# LoRa_Sensor_RevB.net
KiCad netlist of a schematic drawn in EAGLE
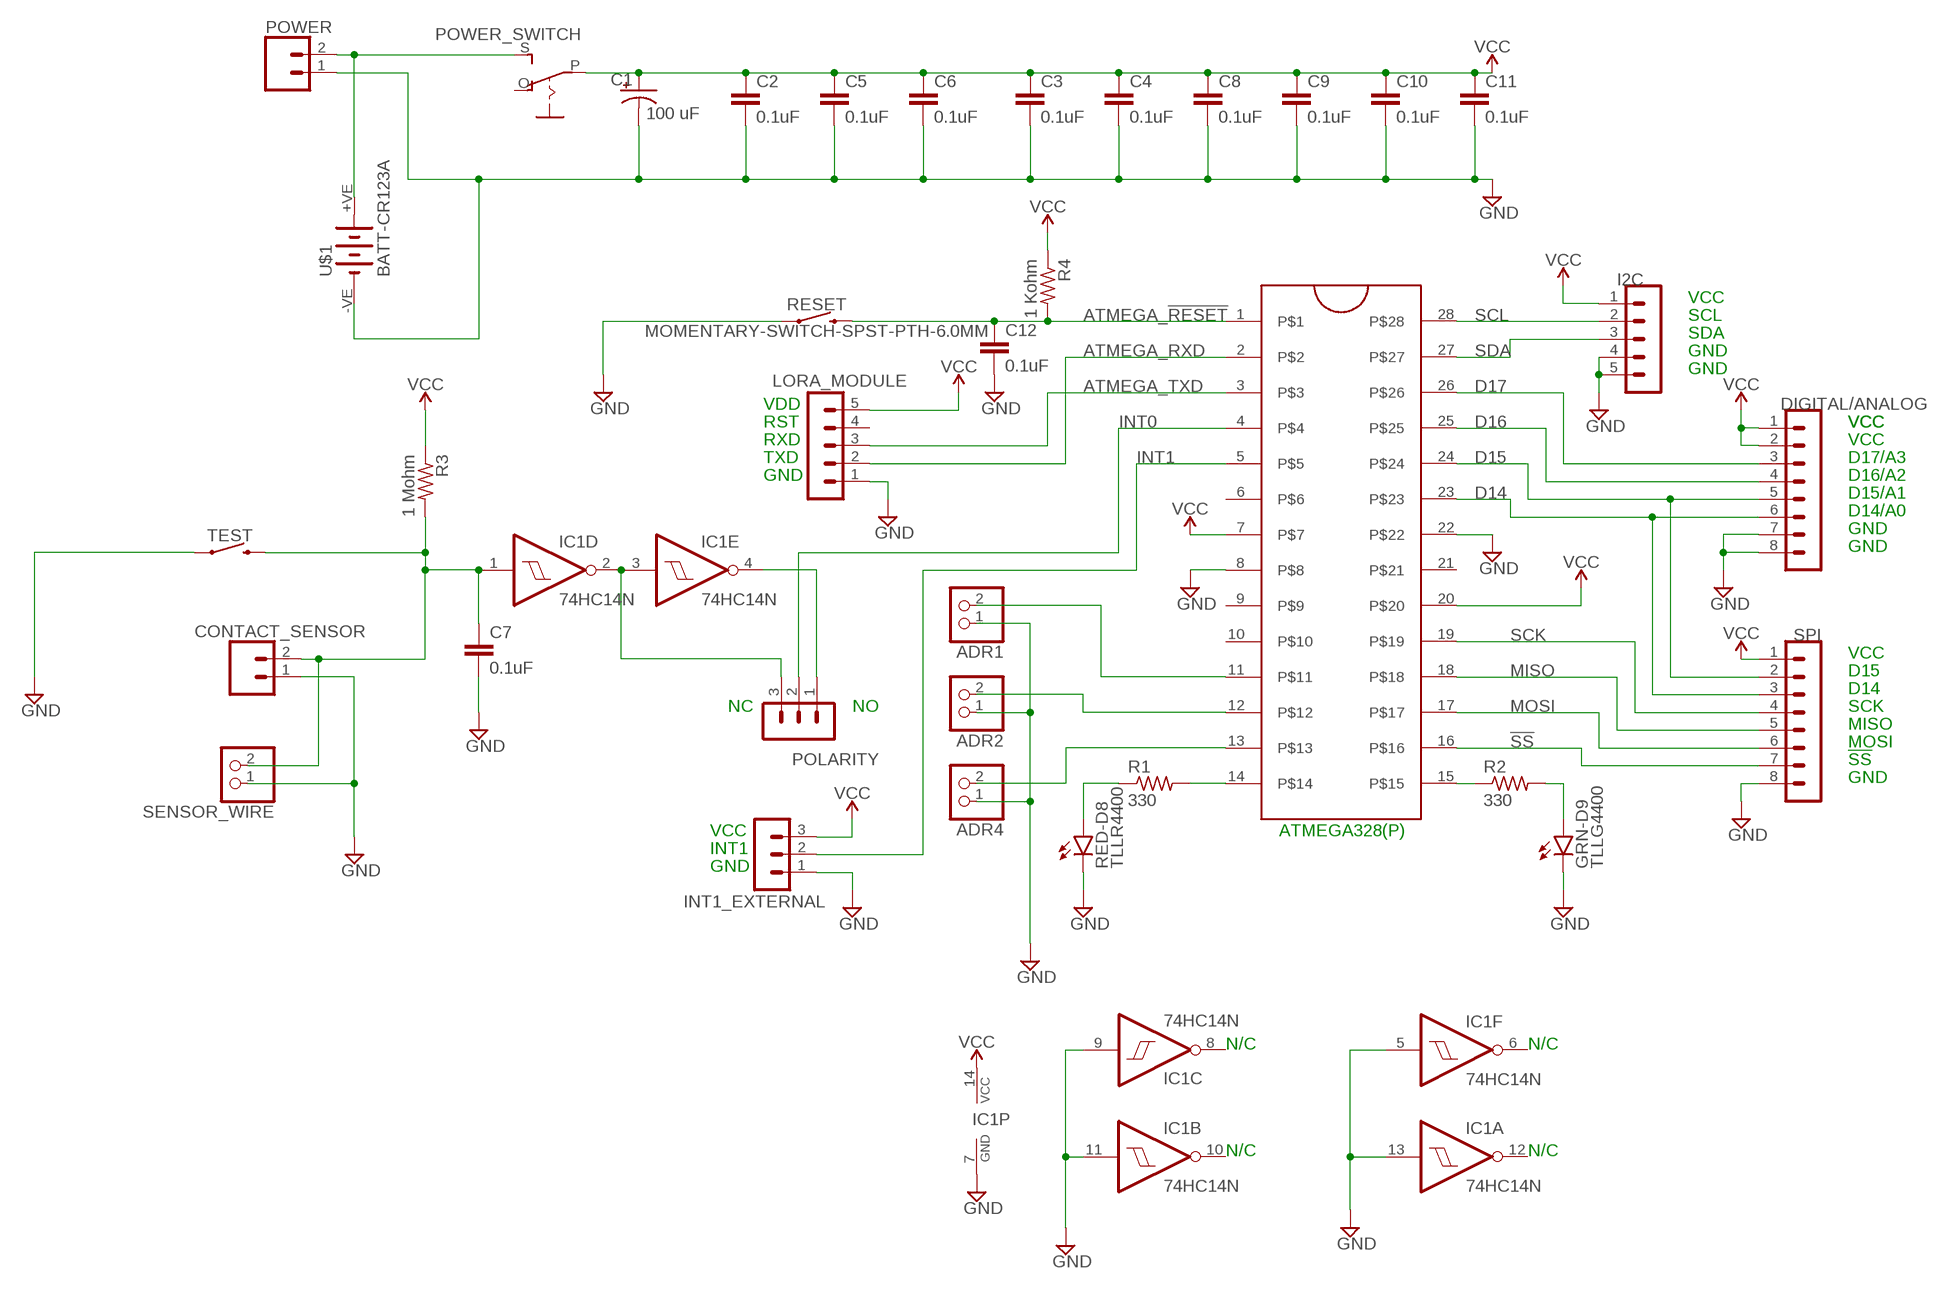
[diagram p0: schematic, sheet 2]

(export (version "E")
  (design (tool "Eeschema 10.0.6"))
  (components
    (comp (ref "ADR1")
      (value "PINHD-1X2")
      (footprint "eagle-import:1X02")
      (libsource (lib "eagle-import") (part "PINHD-1X2"))
    )
    (comp (ref "ADR2")
      (value "PINHD-1X2")
      (footprint "eagle-import:1X02")
      (libsource (lib "eagle-import") (part "PINHD-1X2"))
    )
    (comp (ref "ADR4")
      (value "PINHD-1X2")
      (footprint "eagle-import:1X02")
      (libsource (lib "eagle-import") (part "PINHD-1X2"))
    )
    (comp (ref "C1")
      (value "100 uF")
      (footprint "eagle-import:E2,5-6")
      (libsource (lib "eagle-import") (part "CPOL-USE2.5-6"))
    )
    (comp (ref "C2")
      (value "0.1uF")
      (footprint "eagle-import:CAP-PTH-SMALL-KIT")
      (libsource (lib "eagle-import") (part "0.1UF-KIT-EZ-50V-20%"))
    )
    (comp (ref "C3")
      (value "0.1uF")
      (footprint "eagle-import:CAP-PTH-SMALL-KIT")
      (libsource (lib "eagle-import") (part "0.1UF-KIT-EZ-50V-20%"))
    )
    (comp (ref "C4")
      (value "0.1uF")
      (footprint "eagle-import:CAP-PTH-SMALL-KIT")
      (libsource (lib "eagle-import") (part "0.1UF-KIT-EZ-50V-20%"))
    )
    (comp (ref "C5")
      (value "0.1uF")
      (footprint "eagle-import:CAP-PTH-SMALL-KIT")
      (libsource (lib "eagle-import") (part "0.1UF-KIT-EZ-50V-20%"))
    )
    (comp (ref "C6")
      (value "0.1uF")
      (footprint "eagle-import:CAP-PTH-SMALL-KIT")
      (libsource (lib "eagle-import") (part "0.1UF-KIT-EZ-50V-20%"))
    )
    (comp (ref "C7")
      (value "0.1uF")
      (footprint "eagle-import:CAP-PTH-SMALL-KIT")
      (libsource (lib "eagle-import") (part "0.1UF-KIT-EZ-50V-20%"))
    )
    (comp (ref "C8")
      (value "0.1uF")
      (footprint "eagle-import:CAP-PTH-SMALL-KIT")
      (libsource (lib "eagle-import") (part "0.1UF-KIT-EZ-50V-20%"))
    )
    (comp (ref "C9")
      (value "0.1uF")
      (footprint "eagle-import:CAP-PTH-SMALL-KIT")
      (libsource (lib "eagle-import") (part "0.1UF-KIT-EZ-50V-20%"))
    )
    (comp (ref "C10")
      (value "0.1uF")
      (footprint "eagle-import:CAP-PTH-SMALL-KIT")
      (libsource (lib "eagle-import") (part "0.1UF-KIT-EZ-50V-20%"))
    )
    (comp (ref "C11")
      (value "0.1uF")
      (footprint "eagle-import:CAP-PTH-SMALL-KIT")
      (libsource (lib "eagle-import") (part "0.1UF-KIT-EZ-50V-20%"))
    )
    (comp (ref "C12")
      (value "0.1uF")
      (footprint "eagle-import:CAP-PTH-SMALL-KIT")
      (libsource (lib "eagle-import") (part "0.1UF-KIT-EZ-50V-20%"))
    )
    (comp (ref "CONTACT_SENSOR")
      (value "CONN_023.5MM")
      (footprint "eagle-import:SCREWTERMINAL-3.5MM-2")
      (libsource (lib "eagle-import") (part "CONN_023.5MM"))
    )
    (comp (ref "DIGITAL/ANALOG")
      (value "MA08-1")
      (footprint "eagle-import:MA08-1")
      (libsource (lib "eagle-import") (part "MA08-1"))
    )
    (comp (ref "GRN-D9")
      (value "TLLG4400")
      (footprint "eagle-import:LED3MM")
      (fields (field (name "MF") "VISHAY SEMICONDUCTOR"))
      (libsource (lib "eagle-import") (part "TLLG4400"))
    )
    (comp (ref "I2C")
      (value "MA05-1")
      (footprint "eagle-import:MA05-1")
      (libsource (lib "eagle-import") (part "MA05-1"))
    )
    (comp (ref "IC1")
      (value "74HC14N")
      (footprint "eagle-import:DIL14")
      (libsource (lib "eagle-import") (part "7414NHC"))
    )
    (comp (ref "INT1_EXTERNAL")
      (value "MA03-1")
      (footprint "eagle-import:MA03-1")
      (libsource (lib "eagle-import") (part "MA03-1"))
    )
    (comp (ref "J1")
      (value "ZIFSOCKET-28-3\"")
      (footprint "eagle-import:DIL28-3-ZIF_SOCKET")
      (libsource (lib "eagle-import") (part "ZIFSOCKET-28-3{dblquote}"))
    )
    (comp (ref "LORA_MODULE")
      (value "MA05-1")
      (footprint "eagle-import:MA05-1")
      (libsource (lib "eagle-import") (part "MA05-1"))
    )
    (comp (ref "POLARITY")
      (value "MA03-1")
      (footprint "eagle-import:MA03-1")
      (libsource (lib "eagle-import") (part "MA03-1"))
    )
    (comp (ref "POWER")
      (value "CONN_023.5MM")
      (footprint "eagle-import:SCREWTERMINAL-3.5MM-2")
      (libsource (lib "eagle-import") (part "CONN_023.5MM"))
    )
    (comp (ref "POWER_SWITCH")
      (value "EG1218S")
      (footprint "eagle-import:EG1218")
      (libsource (lib "eagle-import") (part "EG1218S"))
    )
    (comp (ref "R1")
      (value "330")
      (footprint "eagle-import:0309_12")
      (libsource (lib "eagle-import") (part "R-US_0309/12"))
    )
    (comp (ref "R2")
      (value "330")
      (footprint "eagle-import:0309_12")
      (libsource (lib "eagle-import") (part "R-US_0309/12"))
    )
    (comp (ref "R3")
      (value "1 Mohm")
      (footprint "eagle-import:0309_12")
      (libsource (lib "eagle-import") (part "R-US_0309/12"))
    )
    (comp (ref "R4")
      (value "1 Kohm")
      (footprint "eagle-import:0309_12")
      (libsource (lib "eagle-import") (part "R-US_0309/12"))
    )
    (comp (ref "RED-D8")
      (value "TLLR4400")
      (footprint "eagle-import:LED3MM")
      (fields (field (name "MF") "VISHAY SEMICONDUCTOR"))
      (libsource (lib "eagle-import") (part "TLLR4400"))
    )
    (comp (ref "RESET")
      (value "MOMENTARY-SWITCH-SPST-PTH-6.0MM")
      (footprint "eagle-import:TACTILE_SWITCH_PTH_6.0MM")
      (libsource (lib "eagle-import") (part "MOMENTARY-SWITCH-SPST-PTH-6.0MM"))
    )
    (comp (ref "SENSOR_WIRE")
      (value "PINHD-1X2")
      (footprint "eagle-import:1X02")
      (libsource (lib "eagle-import") (part "PINHD-1X2"))
    )
    (comp (ref "SPI")
      (value "MA08-1")
      (footprint "eagle-import:MA08-1")
      (libsource (lib "eagle-import") (part "MA08-1"))
    )
    (comp (ref "TEST")
      (value "MOMENTARY-SWITCH-SPST-PTH-6.0MM")
      (footprint "eagle-import:TACTILE_SWITCH_PTH_6.0MM")
      (libsource (lib "eagle-import") (part "MOMENTARY-SWITCH-SPST-PTH-6.0MM"))
    )
    (comp (ref "U$1")
      (value "BATT-CR123A")
      (footprint "eagle-import:KEYSTONE-2_3A")
      (libsource (lib "eagle-import") (part "BATT-CR123A"))
    )
  )
  (nets
    (net (code "1") (name "ATMEGA_RXD") (class "Default")
      (node (ref "J1") (pin "2") (pinfunction "P$2_2") (pintype "bidirectional"))
      (node (ref "LORA_MODULE") (pin "2") (pinfunction "2_2") (pintype "passive"))
    )
    (net (code "2") (name "ATMEGA_TXD") (class "Default")
      (node (ref "J1") (pin "3") (pinfunction "P$3_3") (pintype "bidirectional"))
      (node (ref "LORA_MODULE") (pin "3") (pinfunction "3_3") (pintype "passive"))
    )
    (net (code "3") (name "ATMEGA_~{RESET}") (class "Default")
      (node (ref "C12") (pin "1") (pinfunction "1_1") (pintype "passive"))
      (node (ref "J1") (pin "1") (pinfunction "P$1_1") (pintype "bidirectional"))
      (node (ref "R4") (pin "2") (pinfunction "2_2") (pintype "passive"))
      (node (ref "RESET") (pin "3") (pinfunction "2_3") (pintype "passive"))
    )
    (net (code "4") (name "D14") (class "Default")
      (node (ref "DIGITAL/ANALOG") (pin "6") (pinfunction "6_6") (pintype "passive"))
      (node (ref "J1") (pin "23") (pinfunction "P$23_23") (pintype "bidirectional"))
      (node (ref "SPI") (pin "3") (pinfunction "3_3") (pintype "passive"))
    )
    (net (code "5") (name "D15") (class "Default")
      (node (ref "DIGITAL/ANALOG") (pin "5") (pinfunction "5_5") (pintype "passive"))
      (node (ref "J1") (pin "24") (pinfunction "P$24_24") (pintype "bidirectional"))
      (node (ref "SPI") (pin "2") (pinfunction "2_2") (pintype "passive"))
    )
    (net (code "6") (name "D16") (class "Default")
      (node (ref "DIGITAL/ANALOG") (pin "4") (pinfunction "4_4") (pintype "passive"))
      (node (ref "J1") (pin "25") (pinfunction "P$25_25") (pintype "bidirectional"))
    )
    (net (code "7") (name "D17") (class "Default")
      (node (ref "DIGITAL/ANALOG") (pin "3") (pinfunction "3_3") (pintype "passive"))
      (node (ref "J1") (pin "26") (pinfunction "P$26_26") (pintype "bidirectional"))
    )
    (net (code "8") (name "GND") (class "Default")
      (node (ref "ADR1") (pin "1") (pinfunction "1_1") (pintype "passive"))
      (node (ref "ADR2") (pin "1") (pinfunction "1_1") (pintype "passive"))
      (node (ref "ADR4") (pin "1") (pinfunction "1_1") (pintype "passive"))
      (node (ref "C1") (pin "-") (pinfunction "-_-") (pintype "passive"))
      (node (ref "C10") (pin "2") (pinfunction "2_2") (pintype "passive"))
      (node (ref "C11") (pin "2") (pinfunction "2_2") (pintype "passive"))
      (node (ref "C12") (pin "2") (pinfunction "2_2") (pintype "passive"))
      (node (ref "C2") (pin "2") (pinfunction "2_2") (pintype "passive"))
      (node (ref "C3") (pin "2") (pinfunction "2_2") (pintype "passive"))
      (node (ref "C4") (pin "2") (pinfunction "2_2") (pintype "passive"))
      (node (ref "C5") (pin "2") (pinfunction "2_2") (pintype "passive"))
      (node (ref "C6") (pin "2") (pinfunction "2_2") (pintype "passive"))
      (node (ref "C7") (pin "2") (pinfunction "2_2") (pintype "passive"))
      (node (ref "C8") (pin "2") (pinfunction "2_2") (pintype "passive"))
      (node (ref "C9") (pin "2") (pinfunction "2_2") (pintype "passive"))
      (node (ref "CONTACT_SENSOR") (pin "1") (pinfunction "1_1") (pintype "passive"))
      (node (ref "DIGITAL/ANALOG") (pin "7") (pinfunction "7_7") (pintype "passive"))
      (node (ref "DIGITAL/ANALOG") (pin "8") (pinfunction "8_8") (pintype "passive"))
      (node (ref "GRN-D9") (pin "K") (pinfunction "C_K") (pintype "passive"))
      (node (ref "I2C") (pin "4") (pinfunction "4_4") (pintype "passive"))
      (node (ref "I2C") (pin "5") (pinfunction "5_5") (pintype "passive"))
      (node (ref "IC1") (pin "11") (pinfunction "I_11") (pintype "input"))
      (node (ref "IC1") (pin "13") (pinfunction "I_13") (pintype "input"))
      (node (ref "IC1") (pin "5") (pinfunction "I_5") (pintype "input"))
      (node (ref "IC1") (pin "7") (pinfunction "GND_7") (pintype "power_in"))
      (node (ref "IC1") (pin "9") (pinfunction "I_9") (pintype "input"))
      (node (ref "INT1_EXTERNAL") (pin "1") (pinfunction "1_1") (pintype "passive"))
      (node (ref "J1") (pin "22") (pinfunction "P$22_22") (pintype "bidirectional"))
      (node (ref "J1") (pin "8") (pinfunction "P$8_8") (pintype "bidirectional"))
      (node (ref "LORA_MODULE") (pin "1") (pinfunction "1_1") (pintype "passive"))
      (node (ref "POWER") (pin "1") (pinfunction "1_1") (pintype "passive"))
      (node (ref "RED-D8") (pin "K") (pinfunction "C_K") (pintype "passive"))
      (node (ref "RESET") (pin "1") (pinfunction "1_1") (pintype "passive"))
      (node (ref "SENSOR_WIRE") (pin "1") (pinfunction "1_1") (pintype "passive"))
      (node (ref "SPI") (pin "8") (pinfunction "8_8") (pintype "passive"))
      (node (ref "TEST") (pin "1") (pinfunction "1_1") (pintype "passive"))
      (node (ref "U$1") (pin "-VE") (pinfunction "-_-VE") (pintype "passive"))
    )
    (net (code "9") (name "INT0") (class "Default")
      (node (ref "J1") (pin "4") (pinfunction "P$4_4") (pintype "bidirectional"))
      (node (ref "POLARITY") (pin "2") (pinfunction "2_2") (pintype "passive"))
    )
    (net (code "10") (name "INT1") (class "Default")
      (node (ref "INT1_EXTERNAL") (pin "2") (pinfunction "2_2") (pintype "passive"))
      (node (ref "J1") (pin "5") (pinfunction "P$5_5") (pintype "bidirectional"))
    )
    (net (code "11") (name "MISO") (class "Default")
      (node (ref "J1") (pin "18") (pinfunction "P$18_18") (pintype "bidirectional"))
      (node (ref "SPI") (pin "5") (pinfunction "5_5") (pintype "passive"))
    )
    (net (code "12") (name "MOSI") (class "Default")
      (node (ref "J1") (pin "17") (pinfunction "P$17_17") (pintype "bidirectional"))
      (node (ref "SPI") (pin "6") (pinfunction "6_6") (pintype "passive"))
    )
    (net (code "13") (name "Net-(GRN-D9-PadA)") (class "Default")
      (node (ref "GRN-D9") (pin "A") (pinfunction "A_A") (pintype "passive"))
      (node (ref "R2") (pin "2") (pinfunction "2_2") (pintype "passive"))
    )
    (net (code "14") (name "Net-(IC1D-I)") (class "Default")
      (node (ref "C7") (pin "1") (pinfunction "1_1") (pintype "passive"))
      (node (ref "CONTACT_SENSOR") (pin "2") (pinfunction "2_2") (pintype "passive"))
      (node (ref "IC1") (pin "1") (pinfunction "I_1") (pintype "input"))
      (node (ref "R3") (pin "2") (pinfunction "2_2") (pintype "passive"))
      (node (ref "SENSOR_WIRE") (pin "2") (pinfunction "2_2") (pintype "passive"))
      (node (ref "TEST") (pin "3") (pinfunction "2_3") (pintype "passive"))
    )
    (net (code "15") (name "Net-(IC1D-O)") (class "Default")
      (node (ref "IC1") (pin "2") (pinfunction "O_2") (pintype "output"))
      (node (ref "IC1") (pin "3") (pinfunction "I_3") (pintype "input"))
      (node (ref "POLARITY") (pin "3") (pinfunction "3_3") (pintype "passive"))
    )
    (net (code "16") (name "Net-(IC1E-O)") (class "Default")
      (node (ref "IC1") (pin "4") (pinfunction "O_4") (pintype "output"))
      (node (ref "POLARITY") (pin "1") (pinfunction "1_1") (pintype "passive"))
    )
    (net (code "17") (name "Net-(J1-P$11)") (class "Default")
      (node (ref "ADR1") (pin "2") (pinfunction "2_2") (pintype "passive"))
      (node (ref "J1") (pin "11") (pinfunction "P$11_11") (pintype "bidirectional"))
    )
    (net (code "18") (name "Net-(J1-P$12)") (class "Default")
      (node (ref "ADR2") (pin "2") (pinfunction "2_2") (pintype "passive"))
      (node (ref "J1") (pin "12") (pinfunction "P$12_12") (pintype "bidirectional"))
    )
    (net (code "19") (name "Net-(J1-P$13)") (class "Default")
      (node (ref "ADR4") (pin "2") (pinfunction "2_2") (pintype "passive"))
      (node (ref "J1") (pin "13") (pinfunction "P$13_13") (pintype "bidirectional"))
    )
    (net (code "20") (name "Net-(J1-P$14)") (class "Default")
      (node (ref "J1") (pin "14") (pinfunction "P$14_14") (pintype "bidirectional"))
      (node (ref "R1") (pin "2") (pinfunction "2_2") (pintype "passive"))
    )
    (net (code "21") (name "Net-(J1-P$15)") (class "Default")
      (node (ref "J1") (pin "15") (pinfunction "P$15_15") (pintype "bidirectional"))
      (node (ref "R2") (pin "1") (pinfunction "1_1") (pintype "passive"))
    )
    (net (code "22") (name "Net-(R1-Pad1)") (class "Default")
      (node (ref "R1") (pin "1") (pinfunction "1_1") (pintype "passive"))
      (node (ref "RED-D8") (pin "A") (pinfunction "A_A") (pintype "passive"))
    )
    (net (code "23") (name "Net-(U$1-+)") (class "Default")
      (node (ref "POWER") (pin "2") (pinfunction "2_2") (pintype "passive"))
      (node (ref "POWER_SWITCH") (pin "S") (pinfunction "S_S") (pintype "passive"))
      (node (ref "U$1") (pin "+VE") (pinfunction "+_+VE") (pintype "passive"))
    )
    (net (code "24") (name "SCK") (class "Default")
      (node (ref "J1") (pin "19") (pinfunction "P$19_19") (pintype "bidirectional"))
      (node (ref "SPI") (pin "4") (pinfunction "4_4") (pintype "passive"))
    )
    (net (code "25") (name "SCL") (class "Default")
      (node (ref "I2C") (pin "2") (pinfunction "2_2") (pintype "passive"))
      (node (ref "J1") (pin "28") (pinfunction "P$28_28") (pintype "bidirectional"))
    )
    (net (code "26") (name "SDA") (class "Default")
      (node (ref "I2C") (pin "3") (pinfunction "3_3") (pintype "passive"))
      (node (ref "J1") (pin "27") (pinfunction "P$27_27") (pintype "bidirectional"))
    )
    (net (code "27") (name "VCC") (class "Default")
      (node (ref "C1") (pin "+") (pinfunction "+_+") (pintype "passive"))
      (node (ref "C10") (pin "1") (pinfunction "1_1") (pintype "passive"))
      (node (ref "C11") (pin "1") (pinfunction "1_1") (pintype "passive"))
      (node (ref "C2") (pin "1") (pinfunction "1_1") (pintype "passive"))
      (node (ref "C3") (pin "1") (pinfunction "1_1") (pintype "passive"))
      (node (ref "C4") (pin "1") (pinfunction "1_1") (pintype "passive"))
      (node (ref "C5") (pin "1") (pinfunction "1_1") (pintype "passive"))
      (node (ref "C6") (pin "1") (pinfunction "1_1") (pintype "passive"))
      (node (ref "C8") (pin "1") (pinfunction "1_1") (pintype "passive"))
      (node (ref "C9") (pin "1") (pinfunction "1_1") (pintype "passive"))
      (node (ref "DIGITAL/ANALOG") (pin "1") (pinfunction "1_1") (pintype "passive"))
      (node (ref "DIGITAL/ANALOG") (pin "2") (pinfunction "2_2") (pintype "passive"))
      (node (ref "I2C") (pin "1") (pinfunction "1_1") (pintype "passive"))
      (node (ref "IC1") (pin "14") (pinfunction "VCC_14") (pintype "power_in"))
      (node (ref "INT1_EXTERNAL") (pin "3") (pinfunction "3_3") (pintype "passive"))
      (node (ref "J1") (pin "20") (pinfunction "P$20_20") (pintype "bidirectional"))
      (node (ref "J1") (pin "7") (pinfunction "P$7_7") (pintype "bidirectional"))
      (node (ref "LORA_MODULE") (pin "5") (pinfunction "5_5") (pintype "passive"))
      (node (ref "POWER_SWITCH") (pin "P") (pinfunction "P_P") (pintype "passive"))
      (node (ref "R3") (pin "1") (pinfunction "1_1") (pintype "passive"))
      (node (ref "R4") (pin "1") (pinfunction "1_1") (pintype "passive"))
      (node (ref "SPI") (pin "1") (pinfunction "1_1") (pintype "passive"))
    )
    (net (code "28") (name "unconnected-(IC1A-O-Pad12)") (class "Default")
      (node (ref "IC1") (pin "12") (pinfunction "O_12") (pintype "output"))
    )
    (net (code "29") (name "unconnected-(IC1B-O-Pad10)") (class "Default")
      (node (ref "IC1") (pin "10") (pinfunction "O_10") (pintype "output"))
    )
    (net (code "30") (name "unconnected-(IC1C-O-Pad8)") (class "Default")
      (node (ref "IC1") (pin "8") (pinfunction "O_8") (pintype "output"))
    )
    (net (code "31") (name "unconnected-(IC1F-O-Pad6)") (class "Default")
      (node (ref "IC1") (pin "6") (pinfunction "O_6") (pintype "output"))
    )
    (net (code "32") (name "unconnected-(J1-P$6-Pad6)") (class "Default")
      (node (ref "J1") (pin "6") (pinfunction "P$6_6") (pintype "bidirectional"))
    )
    (net (code "33") (name "unconnected-(J1-P$9-Pad9)") (class "Default")
      (node (ref "J1") (pin "9") (pinfunction "P$9_9") (pintype "bidirectional"))
    )
    (net (code "34") (name "unconnected-(J1-P$10-Pad10)") (class "Default")
      (node (ref "J1") (pin "10") (pinfunction "P$10_10") (pintype "bidirectional"))
    )
    (net (code "35") (name "unconnected-(J1-P$21-Pad21)") (class "Default")
      (node (ref "J1") (pin "21") (pinfunction "P$21_21") (pintype "bidirectional"))
    )
    (net (code "36") (name "unconnected-(LORA_MODULE-Pad4)") (class "Default")
      (node (ref "LORA_MODULE") (pin "4") (pinfunction "4_4") (pintype "passive"))
    )
    (net (code "37") (name "unconnected-(POWER_SWITCH-PadO)") (class "Default")
      (node (ref "POWER_SWITCH") (pin "O") (pinfunction "O_O") (pintype "passive"))
    )
    (net (code "38") (name "~{SS}") (class "Default")
      (node (ref "J1") (pin "16") (pinfunction "P$16_16") (pintype "bidirectional"))
      (node (ref "SPI") (pin "7") (pinfunction "7_7") (pintype "passive"))
    )
  )
)
